# motor.net
KiCad netlist of a schematic drawn in Altium Designer
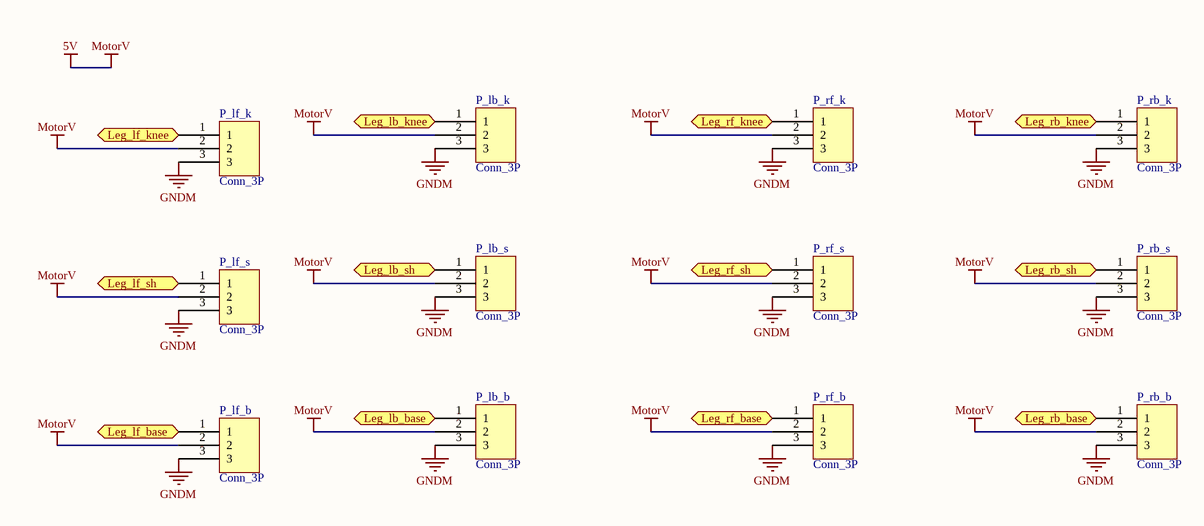
[diagram p0: motor.SchDoc]

(export (version "E")
  (design (tool "Eeschema 10.0.6"))
  (components
    (comp (ref "P_lb_b")
      (value "Conn_3P")
      (footprint "3P_CONN_2mm")
      (libsource (lib "qlib") (part "Conn_3P"))
    )
    (comp (ref "P_lb_k")
      (value "Conn_3P")
      (footprint "3P_CONN_2mm")
      (libsource (lib "qlib") (part "Conn_3P"))
    )
    (comp (ref "P_lb_s")
      (value "Conn_3P")
      (footprint "3P_CONN_2mm")
      (libsource (lib "qlib") (part "Conn_3P"))
    )
    (comp (ref "P_lf_b")
      (value "Conn_3P")
      (footprint "3P_CONN_2mm")
      (libsource (lib "qlib") (part "Conn_3P"))
    )
    (comp (ref "P_lf_k")
      (value "Conn_3P")
      (footprint "3P_CONN_2mm")
      (libsource (lib "qlib") (part "Conn_3P"))
    )
    (comp (ref "P_lf_s")
      (value "Conn_3P")
      (footprint "3P_CONN_2mm")
      (libsource (lib "qlib") (part "Conn_3P"))
    )
    (comp (ref "P_rb_b")
      (value "Conn_3P")
      (footprint "3P_CONN_2mm")
      (libsource (lib "qlib") (part "Conn_3P"))
    )
    (comp (ref "P_rb_k")
      (value "Conn_3P")
      (footprint "3P_CONN_2mm")
      (libsource (lib "qlib") (part "Conn_3P"))
    )
    (comp (ref "P_rb_s")
      (value "Conn_3P")
      (footprint "3P_CONN_2mm")
      (libsource (lib "qlib") (part "Conn_3P"))
    )
    (comp (ref "P_rf_b")
      (value "Conn_3P")
      (footprint "3P_CONN_2mm")
      (libsource (lib "qlib") (part "Conn_3P"))
    )
    (comp (ref "P_rf_k")
      (value "Conn_3P")
      (footprint "3P_CONN_2mm")
      (libsource (lib "qlib") (part "Conn_3P"))
    )
    (comp (ref "P_rf_s")
      (value "Conn_3P")
      (footprint "3P_CONN_2mm")
      (libsource (lib "qlib") (part "Conn_3P"))
    )
  )
  (nets
    (net (code "1") (name "/Leg_lb_base") (class "Default")
      (node (ref "P_lb_b") (pin "1") (pinfunction "1_1") (pintype "passive"))
    )
    (net (code "2") (name "/Leg_lb_knee") (class "Default")
      (node (ref "P_lb_k") (pin "1") (pinfunction "1_1") (pintype "passive"))
    )
    (net (code "3") (name "/Leg_lb_sh") (class "Default")
      (node (ref "P_lb_s") (pin "1") (pinfunction "1_1") (pintype "passive"))
    )
    (net (code "4") (name "/Leg_lf_base") (class "Default")
      (node (ref "P_lf_b") (pin "1") (pinfunction "1_1") (pintype "passive"))
    )
    (net (code "5") (name "/Leg_lf_knee") (class "Default")
      (node (ref "P_lf_k") (pin "1") (pinfunction "1_1") (pintype "passive"))
    )
    (net (code "6") (name "/Leg_lf_sh") (class "Default")
      (node (ref "P_lf_s") (pin "1") (pinfunction "1_1") (pintype "passive"))
    )
    (net (code "7") (name "/Leg_rb_base") (class "Default")
      (node (ref "P_rb_b") (pin "1") (pinfunction "1_1") (pintype "passive"))
    )
    (net (code "8") (name "/Leg_rb_knee") (class "Default")
      (node (ref "P_rb_k") (pin "1") (pinfunction "1_1") (pintype "passive"))
    )
    (net (code "9") (name "/Leg_rb_sh") (class "Default")
      (node (ref "P_rb_s") (pin "1") (pinfunction "1_1") (pintype "passive"))
    )
    (net (code "10") (name "/Leg_rf_base") (class "Default")
      (node (ref "P_rf_b") (pin "1") (pinfunction "1_1") (pintype "passive"))
    )
    (net (code "11") (name "/Leg_rf_knee") (class "Default")
      (node (ref "P_rf_k") (pin "1") (pinfunction "1_1") (pintype "passive"))
    )
    (net (code "12") (name "/Leg_rf_sh") (class "Default")
      (node (ref "P_rf_s") (pin "1") (pinfunction "1_1") (pintype "passive"))
    )
    (net (code "13") (name "5V") (class "Default")
      (node (ref "P_lb_b") (pin "2") (pinfunction "2_2") (pintype "passive"))
      (node (ref "P_lb_k") (pin "2") (pinfunction "2_2") (pintype "passive"))
      (node (ref "P_lb_s") (pin "2") (pinfunction "2_2") (pintype "passive"))
      (node (ref "P_lf_b") (pin "2") (pinfunction "2_2") (pintype "passive"))
      (node (ref "P_lf_k") (pin "2") (pinfunction "2_2") (pintype "passive"))
      (node (ref "P_lf_s") (pin "2") (pinfunction "2_2") (pintype "passive"))
      (node (ref "P_rb_b") (pin "2") (pinfunction "2_2") (pintype "passive"))
      (node (ref "P_rb_k") (pin "2") (pinfunction "2_2") (pintype "passive"))
      (node (ref "P_rb_s") (pin "2") (pinfunction "2_2") (pintype "passive"))
      (node (ref "P_rf_b") (pin "2") (pinfunction "2_2") (pintype "passive"))
      (node (ref "P_rf_k") (pin "2") (pinfunction "2_2") (pintype "passive"))
      (node (ref "P_rf_s") (pin "2") (pinfunction "2_2") (pintype "passive"))
    )
    (net (code "14") (name "GNDM") (class "Default")
      (node (ref "P_lb_b") (pin "3") (pinfunction "3_3") (pintype "passive"))
      (node (ref "P_lb_k") (pin "3") (pinfunction "3_3") (pintype "passive"))
      (node (ref "P_lb_s") (pin "3") (pinfunction "3_3") (pintype "passive"))
      (node (ref "P_lf_b") (pin "3") (pinfunction "3_3") (pintype "passive"))
      (node (ref "P_lf_k") (pin "3") (pinfunction "3_3") (pintype "passive"))
      (node (ref "P_lf_s") (pin "3") (pinfunction "3_3") (pintype "passive"))
      (node (ref "P_rb_b") (pin "3") (pinfunction "3_3") (pintype "passive"))
      (node (ref "P_rb_k") (pin "3") (pinfunction "3_3") (pintype "passive"))
      (node (ref "P_rb_s") (pin "3") (pinfunction "3_3") (pintype "passive"))
      (node (ref "P_rf_b") (pin "3") (pinfunction "3_3") (pintype "passive"))
      (node (ref "P_rf_k") (pin "3") (pinfunction "3_3") (pintype "passive"))
      (node (ref "P_rf_s") (pin "3") (pinfunction "3_3") (pintype "passive"))
    )
  )
)
